# Arduino_FPGA_Level_Translation.net
KiCad netlist of a schematic drawn in Altium Designer
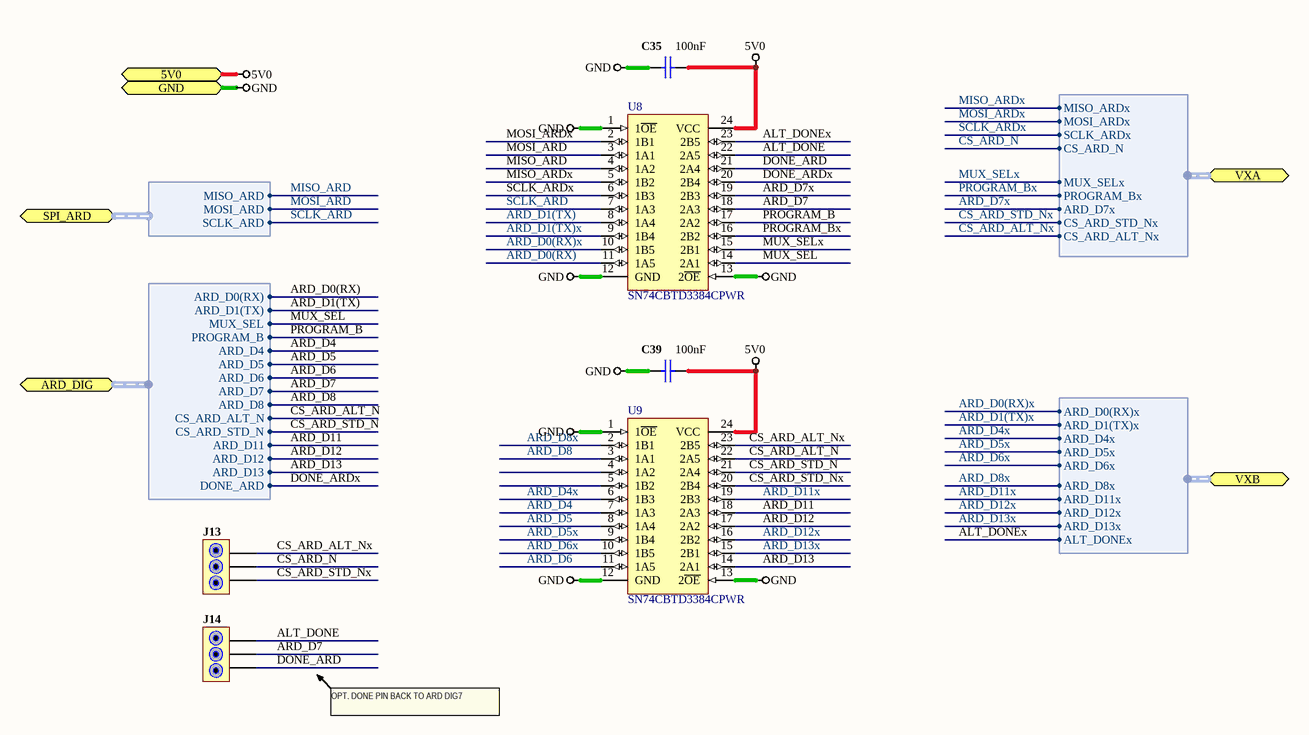
[diagram p0: Arduino FPGA Level Translation.SchDoc]

(export (version "E")
  (design (tool "Eeschema 10.0.6"))
  (components
    (comp (ref "C35")
      (value "100nF")
      (footprint "CAPC0402(1005)60_L")
      (fields
        (field (name "TOLERANCE") "±10%")
        (field (name "MANUFACTURER PART NUMBER") "C0402C104K8PACTU")
        (field (name "Comment") "CAP 100nF 16V 0402(1005)")
      )
      (libsource (lib "Component_Database") (part "CAP_NP"))
    )
    (comp (ref "C39")
      (value "100nF")
      (footprint "CAPC0402(1005)60_L")
      (fields
        (field (name "TOLERANCE") "±10%")
        (field (name "MANUFACTURER PART NUMBER") "C0402C104K8PACTU")
        (field (name "Comment") "CAP 100nF 16V 0402(1005)")
      )
      (libsource (lib "Component_Database") (part "CAP_NP"))
    )
    (comp (ref "J13")
      (value "3-WAY JUMPER")
      (footprint "HDR1X3")
      (description "3-Way Jumper - Center Output")
      (fields (field (name "MANUFACTURER PART NUMBER") "71417-103HLF"))
      (libsource (lib "3-WAY JUMPER") (part "3-WAY JUMPER"))
    )
    (comp (ref "J14")
      (value "3-WAY JUMPER")
      (footprint "HDR1X3")
      (description "3-Way Jumper - Center Output")
      (fields (field (name "MANUFACTURER PART NUMBER") "71417-103HLF"))
      (libsource (lib "3-WAY JUMPER") (part "3-WAY JUMPER"))
    )
    (comp (ref "U8")
      (value "SN74CBTD3384CPWR")
      (footprint "TSOP65P620X120-24N")
      (description "10-BIT FET BUS SWITCH WITH LEVEL SHIFTING")
      (fields
        (field (name "MANUFACTURER PART NUMBER") "SN74CBTD3861PWR")
        (field (name "MANUFACTURER") "Texas Instruments")
      )
      (libsource (lib "SN74CBTD3384CPWR") (part "SN74CBTD3384CPWR"))
    )
    (comp (ref "U9")
      (value "SN74CBTD3384CPWR")
      (footprint "TSOP65P620X120-24N")
      (description "10-BIT FET BUS SWITCH WITH LEVEL SHIFTING")
      (fields
        (field (name "MANUFACTURER PART NUMBER") "SN74CBTD3861PWR")
        (field (name "MANUFACTURER") "Texas Instruments")
      )
      (libsource (lib "SN74CBTD3384CPWR") (part "SN74CBTD3384CPWR"))
    )
  )
  (nets
    (net (code "5") (name "/ALT_DONE") (class "Default")
      (node (ref "J14") (pin "3") (pinfunction "3_3") (pintype "passive"))
      (node (ref "U8") (pin "22") (pinfunction "2A5_22") (pintype "bidirectional"))
    )
    (net (code "6") (name "/ALT_DONEx") (class "Default")
      (node (ref "U8") (pin "23") (pinfunction "2B5_23") (pintype "bidirectional"))
    )
    (net (code "7") (name "/ARD_D0(RX)") (class "Default")
      (node (ref "U8") (pin "11") (pinfunction "1A5_11") (pintype "bidirectional"))
    )
    (net (code "8") (name "/ARD_D0(RX)x") (class "Default")
      (node (ref "U8") (pin "10") (pinfunction "1B5_10") (pintype "bidirectional"))
    )
    (net (code "9") (name "/ARD_D1(TX)") (class "Default")
      (node (ref "U8") (pin "8") (pinfunction "1A4_8") (pintype "bidirectional"))
    )
    (net (code "10") (name "/ARD_D1(TX)x") (class "Default")
      (node (ref "U8") (pin "9") (pinfunction "1B4_9") (pintype "bidirectional"))
    )
    (net (code "11") (name "/ARD_D4") (class "Default")
      (node (ref "U9") (pin "7") (pinfunction "1A3_7") (pintype "bidirectional"))
    )
    (net (code "12") (name "/ARD_D4x") (class "Default")
      (node (ref "U9") (pin "6") (pinfunction "1B3_6") (pintype "bidirectional"))
    )
    (net (code "13") (name "/ARD_D5") (class "Default")
      (node (ref "U9") (pin "8") (pinfunction "1A4_8") (pintype "bidirectional"))
    )
    (net (code "14") (name "/ARD_D5x") (class "Default")
      (node (ref "U9") (pin "9") (pinfunction "1B4_9") (pintype "bidirectional"))
    )
    (net (code "15") (name "/ARD_D6") (class "Default")
      (node (ref "U9") (pin "11") (pinfunction "1A5_11") (pintype "bidirectional"))
    )
    (net (code "16") (name "/ARD_D6x") (class "Default")
      (node (ref "U9") (pin "10") (pinfunction "1B5_10") (pintype "bidirectional"))
    )
    (net (code "17") (name "/ARD_D7") (class "Default")
      (node (ref "J14") (pin "2") (pinfunction "2_2") (pintype "passive"))
      (node (ref "U8") (pin "18") (pinfunction "2A3_18") (pintype "bidirectional"))
    )
    (net (code "18") (name "/ARD_D7x") (class "Default")
      (node (ref "U8") (pin "19") (pinfunction "2B3_19") (pintype "bidirectional"))
    )
    (net (code "19") (name "/ARD_D8") (class "Default")
      (node (ref "U9") (pin "3") (pinfunction "1A1_3") (pintype "bidirectional"))
    )
    (net (code "20") (name "/ARD_D8x") (class "Default")
      (node (ref "U9") (pin "2") (pinfunction "1B1_2") (pintype "bidirectional"))
    )
    (net (code "21") (name "/ARD_D11") (class "Default")
      (node (ref "U9") (pin "18") (pinfunction "2A3_18") (pintype "bidirectional"))
    )
    (net (code "22") (name "/ARD_D11x") (class "Default")
      (node (ref "U9") (pin "19") (pinfunction "2B3_19") (pintype "bidirectional"))
    )
    (net (code "23") (name "/ARD_D12") (class "Default")
      (node (ref "U9") (pin "17") (pinfunction "2A2_17") (pintype "bidirectional"))
    )
    (net (code "24") (name "/ARD_D12x") (class "Default")
      (node (ref "U9") (pin "16") (pinfunction "2B2_16") (pintype "bidirectional"))
    )
    (net (code "25") (name "/ARD_D13") (class "Default")
      (node (ref "U9") (pin "14") (pinfunction "2A1_14") (pintype "bidirectional"))
    )
    (net (code "26") (name "/ARD_D13x") (class "Default")
      (node (ref "U9") (pin "15") (pinfunction "2B1_15") (pintype "bidirectional"))
    )
    (net (code "27") (name "/CS_ARD_ALT_N") (class "Default")
      (node (ref "U9") (pin "22") (pinfunction "2A5_22") (pintype "bidirectional"))
    )
    (net (code "28") (name "/CS_ARD_ALT_Nx") (class "Default")
      (node (ref "J13") (pin "3") (pinfunction "3_3") (pintype "passive"))
      (node (ref "U9") (pin "23") (pinfunction "2B5_23") (pintype "bidirectional"))
    )
    (net (code "29") (name "/CS_ARD_N") (class "Default")
      (node (ref "J13") (pin "2") (pinfunction "2_2") (pintype "passive"))
    )
    (net (code "30") (name "/CS_ARD_STD_N") (class "Default")
      (node (ref "U9") (pin "21") (pinfunction "2A4_21") (pintype "bidirectional"))
    )
    (net (code "31") (name "/CS_ARD_STD_Nx") (class "Default")
      (node (ref "J13") (pin "1") (pinfunction "1_1") (pintype "passive"))
      (node (ref "U9") (pin "20") (pinfunction "2B4_20") (pintype "bidirectional"))
    )
    (net (code "32") (name "/DONE_ARD") (class "Default")
      (node (ref "J14") (pin "1") (pinfunction "1_1") (pintype "passive"))
      (node (ref "U8") (pin "21") (pinfunction "2A4_21") (pintype "bidirectional"))
    )
    (net (code "33") (name "/DONE_ARDx") (class "Default")
      (node (ref "U8") (pin "20") (pinfunction "2B4_20") (pintype "bidirectional"))
    )
    (net (code "34") (name "/MISO_ARD") (class "Default")
      (node (ref "U8") (pin "4") (pinfunction "1A2_4") (pintype "bidirectional"))
    )
    (net (code "35") (name "/MISO_ARDx") (class "Default")
      (node (ref "U8") (pin "5") (pinfunction "1B2_5") (pintype "bidirectional"))
    )
    (net (code "36") (name "/MOSI_ARD") (class "Default")
      (node (ref "U8") (pin "3") (pinfunction "1A1_3") (pintype "bidirectional"))
    )
    (net (code "37") (name "/MOSI_ARDx") (class "Default")
      (node (ref "U8") (pin "2") (pinfunction "1B1_2") (pintype "bidirectional"))
    )
    (net (code "38") (name "/MUX_SEL") (class "Default")
      (node (ref "U8") (pin "14") (pinfunction "2A1_14") (pintype "bidirectional"))
    )
    (net (code "39") (name "/MUX_SELx") (class "Default")
      (node (ref "U8") (pin "15") (pinfunction "2B1_15") (pintype "bidirectional"))
    )
    (net (code "40") (name "/PROGRAM_B") (class "Default")
      (node (ref "U8") (pin "17") (pinfunction "2A2_17") (pintype "bidirectional"))
    )
    (net (code "41") (name "/PROGRAM_Bx") (class "Default")
      (node (ref "U8") (pin "16") (pinfunction "2B2_16") (pintype "bidirectional"))
    )
    (net (code "42") (name "/SCLK_ARD") (class "Default")
      (node (ref "U8") (pin "7") (pinfunction "1A3_7") (pintype "bidirectional"))
    )
    (net (code "43") (name "/SCLK_ARDx") (class "Default")
      (node (ref "U8") (pin "6") (pinfunction "1B3_6") (pintype "bidirectional"))
    )
    (net (code "48") (name "5V0") (class "Default")
      (node (ref "C35") (pin "2") (pinfunction "2_2") (pintype "passive"))
      (node (ref "C39") (pin "2") (pinfunction "2_2") (pintype "passive"))
      (node (ref "U8") (pin "24") (pinfunction "VCC_24") (pintype "passive"))
      (node (ref "U9") (pin "24") (pinfunction "VCC_24") (pintype "passive"))
    )
    (net (code "49") (name "GND") (class "Default")
      (node (ref "C35") (pin "1") (pinfunction "1_1") (pintype "passive"))
      (node (ref "C39") (pin "1") (pinfunction "1_1") (pintype "passive"))
      (node (ref "U8") (pin "1") (pinfunction "1~{OE}_1") (pintype "input"))
      (node (ref "U8") (pin "12") (pinfunction "GND_12") (pintype "passive"))
      (node (ref "U8") (pin "13") (pinfunction "2~{OE}_13") (pintype "input"))
      (node (ref "U9") (pin "1") (pinfunction "1~{OE}_1") (pintype "input"))
      (node (ref "U9") (pin "12") (pinfunction "GND_12") (pintype "passive"))
      (node (ref "U9") (pin "13") (pinfunction "2~{OE}_13") (pintype "input"))
    )
    (net (code "50") (name "unconnected-(U9-1A2-Pad4)") (class "Default")
      (node (ref "U9") (pin "4") (pinfunction "1A2_4") (pintype "bidirectional"))
    )
    (net (code "51") (name "unconnected-(U9-1B2-Pad5)") (class "Default")
      (node (ref "U9") (pin "5") (pinfunction "1B2_5") (pintype "bidirectional"))
    )
  )
)
